# cvpal_v01.net
KiCad netlist of a schematic drawn in EAGLE
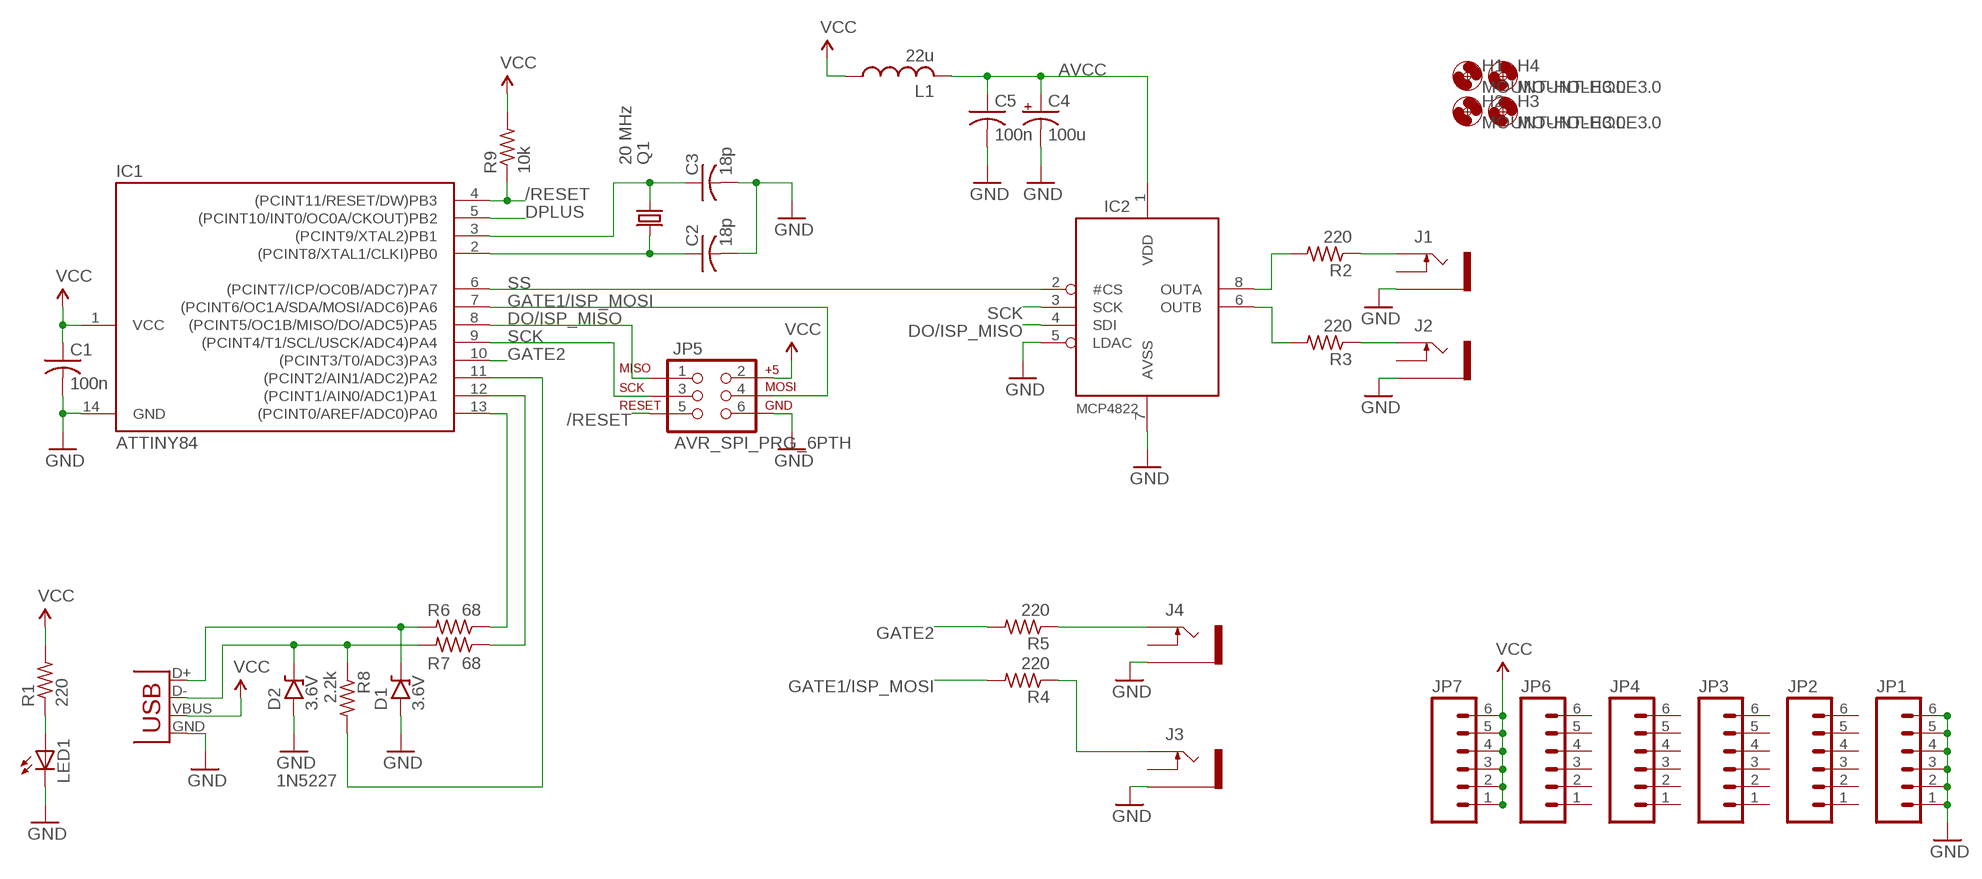
[diagram p0: schematic, sheet 1]

(export (version "E")
  (design (tool "Eeschema 10.0.6"))
  (components
    (comp (ref "C1")
      (value "100n")
      (footprint "eagle-import:C025-025X050")
      (libsource (lib "eagle-import") (part "C-US025-025X050"))
    )
    (comp (ref "C2")
      (value "18p")
      (footprint "eagle-import:C025-025X050")
      (libsource (lib "eagle-import") (part "C-US025-025X050"))
    )
    (comp (ref "C3")
      (value "18p")
      (footprint "eagle-import:C025-025X050")
      (libsource (lib "eagle-import") (part "C-US025-025X050"))
    )
    (comp (ref "C4")
      (value "100u")
      (footprint "eagle-import:E2,5-7")
      (libsource (lib "eagle-import") (part "CPOL-USE2.5-7"))
    )
    (comp (ref "C5")
      (value "100n")
      (footprint "eagle-import:C025-025X050")
      (libsource (lib "eagle-import") (part "C-US025-025X050"))
    )
    (comp (ref "D1")
      (value "3.6V")
      (footprint "eagle-import:D-5")
      (libsource (lib "eagle-import") (part "1N47XXDO35"))
    )
    (comp (ref "D2")
      (value "3.6V")
      (footprint "eagle-import:D-5")
      (libsource (lib "eagle-import") (part "1N47XXDO35"))
    )
    (comp (ref "H1")
      (value "MOUNT-HOLE3.0")
      (footprint "eagle-import:3,0")
      (libsource (lib "eagle-import") (part "MOUNT-HOLE3.0"))
    )
    (comp (ref "H2")
      (value "MOUNT-HOLE3.0")
      (footprint "eagle-import:3,0")
      (libsource (lib "eagle-import") (part "MOUNT-HOLE3.0"))
    )
    (comp (ref "H3")
      (value "MOUNT-HOLE3.0")
      (footprint "eagle-import:3,0")
      (libsource (lib "eagle-import") (part "MOUNT-HOLE3.0"))
    )
    (comp (ref "H4")
      (value "MOUNT-HOLE3.0")
      (footprint "eagle-import:3,0")
      (libsource (lib "eagle-import") (part "MOUNT-HOLE3.0"))
    )
    (comp (ref "IC1")
      (value "ATTINY84")
      (footprint "eagle-import:DIL14")
      (libsource (lib "eagle-import") (part "ATTINY24/44/84-PU"))
    )
    (comp (ref "IC2")
      (value "MCP4822")
      (footprint "eagle-import:DIL08")
      (libsource (lib "eagle-import") (part "MCP4822"))
    )
    (comp (ref "J1")
      (value "1503_12")
      (footprint "eagle-import:1503_12")
      (libsource (lib "eagle-import") (part "1503_12"))
    )
    (comp (ref "J2")
      (value "1503_12")
      (footprint "eagle-import:1503_12")
      (libsource (lib "eagle-import") (part "1503_12"))
    )
    (comp (ref "J3")
      (value "1503_12")
      (footprint "eagle-import:1503_12")
      (libsource (lib "eagle-import") (part "1503_12"))
    )
    (comp (ref "J4")
      (value "1503_12")
      (footprint "eagle-import:1503_12")
      (libsource (lib "eagle-import") (part "1503_12"))
    )
    (comp (ref "JP1")
      (value "M06SIP")
      (footprint "eagle-import:1X06")
      (libsource (lib "eagle-import") (part "M06SIP"))
    )
    (comp (ref "JP2")
      (value "M06SIP")
      (footprint "eagle-import:1X06")
      (libsource (lib "eagle-import") (part "M06SIP"))
    )
    (comp (ref "JP3")
      (value "M06SIP")
      (footprint "eagle-import:1X06")
      (libsource (lib "eagle-import") (part "M06SIP"))
    )
    (comp (ref "JP4")
      (value "M06SIP")
      (footprint "eagle-import:1X06")
      (libsource (lib "eagle-import") (part "M06SIP"))
    )
    (comp (ref "JP5")
      (value "AVR_SPI_PRG_6PTH")
      (footprint "eagle-import:2X3")
      (libsource (lib "eagle-import") (part "AVR_SPI_PRG_6PTH"))
    )
    (comp (ref "JP6")
      (value "M06SIP")
      (footprint "eagle-import:1X06")
      (libsource (lib "eagle-import") (part "M06SIP"))
    )
    (comp (ref "JP7")
      (value "M06SIP")
      (footprint "eagle-import:1X06")
      (libsource (lib "eagle-import") (part "M06SIP"))
    )
    (comp (ref "L1")
      (value "22u")
      (footprint "eagle-import:0207_10")
      (libsource (lib "eagle-import") (part "L-US0207/10"))
    )
    (comp (ref "LED1")
      (value "LED5MM")
      (footprint "eagle-import:LED5MM")
      (libsource (lib "eagle-import") (part "LED5MM"))
    )
    (comp (ref "Q1")
      (value "20 MHz")
      (footprint "eagle-import:HC49_S")
      (libsource (lib "eagle-import") (part "CRYSTALHC49S"))
    )
    (comp (ref "R1")
      (value "220")
      (footprint "eagle-import:0204_7")
      (libsource (lib "eagle-import") (part "R-US_0204/7"))
    )
    (comp (ref "R2")
      (value "220")
      (footprint "eagle-import:0204_7")
      (libsource (lib "eagle-import") (part "R-US_0204/7"))
    )
    (comp (ref "R3")
      (value "220")
      (footprint "eagle-import:0204_7")
      (libsource (lib "eagle-import") (part "R-US_0204/7"))
    )
    (comp (ref "R4")
      (value "220")
      (footprint "eagle-import:0204_7")
      (libsource (lib "eagle-import") (part "R-US_0204/7"))
    )
    (comp (ref "R5")
      (value "220")
      (footprint "eagle-import:0204_7")
      (libsource (lib "eagle-import") (part "R-US_0204/7"))
    )
    (comp (ref "R6")
      (value "68")
      (footprint "eagle-import:0204_7")
      (libsource (lib "eagle-import") (part "R-US_0204/7"))
    )
    (comp (ref "R7")
      (value "68")
      (footprint "eagle-import:0204_7")
      (libsource (lib "eagle-import") (part "R-US_0204/7"))
    )
    (comp (ref "R8")
      (value "2.2k")
      (footprint "eagle-import:0204_7")
      (libsource (lib "eagle-import") (part "R-US_0204/7"))
    )
    (comp (ref "R9")
      (value "10k")
      (footprint "eagle-import:0204_7")
      (libsource (lib "eagle-import") (part "R-US_0204/7"))
    )
    (comp (ref "X2")
      (value "USBPTH")
      (footprint "eagle-import:USB-B-PTH")
      (libsource (lib "eagle-import") (part "USBPTH"))
    )
  )
  (nets
    (net (code "1") (name "/AVCC") (class "Default")
      (node (ref "C4") (pin "+") (pinfunction "+_+") (pintype "passive"))
      (node (ref "C5") (pin "1") (pinfunction "1_1") (pintype "passive"))
      (node (ref "IC2") (pin "1") (pinfunction "VDD_1") (pintype "power_in"))
      (node (ref "L1") (pin "2") (pinfunction "2_2") (pintype "passive"))
    )
    (net (code "2") (name "/DO{slash}ISP_MISO") (class "Default")
      (node (ref "IC1") (pin "8") (pinfunction "(PCINT5/OC1B/MISO/DO/ADC5)PA5_8") (pintype "bidirectional"))
      (node (ref "IC2") (pin "4") (pinfunction "SDI_4") (pintype "input"))
      (node (ref "JP5") (pin "1") (pinfunction "1_1") (pintype "passive"))
    )
    (net (code "3") (name "/DPLUS") (class "Default")
      (node (ref "IC1") (pin "13") (pinfunction "(PCINT0/AREF/ADC0)PA0_13") (pintype "bidirectional"))
      (node (ref "IC1") (pin "5") (pinfunction "(PCINT10/INT0/OC0A/CKOUT)PB2_5") (pintype "bidirectional"))
      (node (ref "R6") (pin "1") (pinfunction "1_1") (pintype "passive"))
    )
    (net (code "4") (name "/GATE1{slash}ISP_MOSI") (class "Default")
      (node (ref "IC1") (pin "7") (pinfunction "(PCINT6/OC1A/SDA/MOSI/ADC6)PA6_7") (pintype "bidirectional"))
      (node (ref "JP5") (pin "4") (pinfunction "4_4") (pintype "passive"))
      (node (ref "R4") (pin "2") (pinfunction "2_2") (pintype "passive"))
    )
    (net (code "5") (name "/GATE2") (class "Default")
      (node (ref "IC1") (pin "10") (pinfunction "(PCINT3/T0/ADC3)PA3_10") (pintype "bidirectional"))
      (node (ref "R5") (pin "2") (pinfunction "2_2") (pintype "passive"))
    )
    (net (code "6") (name "/SCK") (class "Default")
      (node (ref "IC1") (pin "9") (pinfunction "(PCINT4/T1/SCL/USCK/ADC4)PA4_9") (pintype "bidirectional"))
      (node (ref "IC2") (pin "3") (pinfunction "SCK_3") (pintype "input"))
      (node (ref "JP5") (pin "3") (pinfunction "3_3") (pintype "passive"))
    )
    (net (code "7") (name "/SS") (class "Default")
      (node (ref "IC1") (pin "6") (pinfunction "(PCINT7/ICP/OC0B/ADC7)PA7_6") (pintype "bidirectional"))
      (node (ref "IC2") (pin "2") (pinfunction "#CS_2") (pintype "input"))
    )
    (net (code "8") (name "/{slash}RESET") (class "Default")
      (node (ref "IC1") (pin "4") (pinfunction "(PCINT11/RESET/DW)PB3_4") (pintype "bidirectional"))
      (node (ref "JP5") (pin "5") (pinfunction "5_5") (pintype "passive"))
      (node (ref "R9") (pin "1") (pinfunction "1_1") (pintype "passive"))
    )
    (net (code "9") (name "GND") (class "Default")
      (node (ref "C1") (pin "2") (pinfunction "2_2") (pintype "passive"))
      (node (ref "C2") (pin "2") (pinfunction "2_2") (pintype "passive"))
      (node (ref "C3") (pin "2") (pinfunction "2_2") (pintype "passive"))
      (node (ref "C4") (pin "-") (pinfunction "-_-") (pintype "passive"))
      (node (ref "C5") (pin "2") (pinfunction "2_2") (pintype "passive"))
      (node (ref "D1") (pin "A") (pinfunction "A_A") (pintype "passive"))
      (node (ref "D2") (pin "A") (pinfunction "A_A") (pintype "passive"))
      (node (ref "IC1") (pin "14") (pinfunction "GND_14") (pintype "power_in"))
      (node (ref "IC2") (pin "5") (pinfunction "LDAC_5") (pintype "input"))
      (node (ref "IC2") (pin "7") (pinfunction "AVSS_7") (pintype "power_in"))
      (node (ref "J1") (pin "5") (pinfunction "1_5") (pintype "passive"))
      (node (ref "J2") (pin "5") (pinfunction "1_5") (pintype "passive"))
      (node (ref "J3") (pin "5") (pinfunction "1_5") (pintype "passive"))
      (node (ref "J4") (pin "5") (pinfunction "1_5") (pintype "passive"))
      (node (ref "JP1") (pin "1") (pinfunction "1_1") (pintype "passive"))
      (node (ref "JP1") (pin "2") (pinfunction "2_2") (pintype "passive"))
      (node (ref "JP1") (pin "3") (pinfunction "3_3") (pintype "passive"))
      (node (ref "JP1") (pin "4") (pinfunction "4_4") (pintype "passive"))
      (node (ref "JP1") (pin "5") (pinfunction "5_5") (pintype "passive"))
      (node (ref "JP1") (pin "6") (pinfunction "6_6") (pintype "passive"))
      (node (ref "JP5") (pin "6") (pinfunction "6_6") (pintype "passive"))
      (node (ref "LED1") (pin "K") (pinfunction "C_K") (pintype "passive"))
      (node (ref "X2") (pin "GND") (pinfunction "GND_GND") (pintype "bidirectional"))
    )
    (net (code "10") (name "Net-(D1-PadC)") (class "Default")
      (node (ref "D1") (pin "C") (pinfunction "C_C") (pintype "passive"))
      (node (ref "R6") (pin "2") (pinfunction "2_2") (pintype "passive"))
      (node (ref "X2") (pin "D+") (pinfunction "D+_D+") (pintype "bidirectional"))
    )
    (net (code "11") (name "Net-(D2-PadC)") (class "Default")
      (node (ref "D2") (pin "C") (pinfunction "C_C") (pintype "passive"))
      (node (ref "R7") (pin "2") (pinfunction "2_2") (pintype "passive"))
      (node (ref "R8") (pin "1") (pinfunction "1_1") (pintype "passive"))
      (node (ref "X2") (pin "D-") (pinfunction "D-_D-") (pintype "bidirectional"))
    )
    (net (code "12") (name "Net-(IC1-(PCINT1{slash}AIN0{slash}ADC1)PA1)") (class "Default")
      (node (ref "IC1") (pin "12") (pinfunction "(PCINT1/AIN0/ADC1)PA1_12") (pintype "bidirectional"))
      (node (ref "R7") (pin "1") (pinfunction "1_1") (pintype "passive"))
    )
    (net (code "13") (name "Net-(IC1-(PCINT2{slash}AIN1{slash}ADC2)PA2)") (class "Default")
      (node (ref "IC1") (pin "11") (pinfunction "(PCINT2/AIN1/ADC2)PA2_11") (pintype "bidirectional"))
      (node (ref "R8") (pin "2") (pinfunction "2_2") (pintype "passive"))
    )
    (net (code "14") (name "Net-(IC1-(PCINT8{slash}XTAL1{slash}CLKI)PB0)") (class "Default")
      (node (ref "C2") (pin "1") (pinfunction "1_1") (pintype "passive"))
      (node (ref "IC1") (pin "2") (pinfunction "(PCINT8/XTAL1/CLKI)PB0_2") (pintype "bidirectional"))
      (node (ref "Q1") (pin "2") (pinfunction "2_2") (pintype "passive"))
    )
    (net (code "15") (name "Net-(IC1-(PCINT9{slash}XTAL2)PB1)") (class "Default")
      (node (ref "C3") (pin "1") (pinfunction "1_1") (pintype "passive"))
      (node (ref "IC1") (pin "3") (pinfunction "(PCINT9/XTAL2)PB1_3") (pintype "bidirectional"))
      (node (ref "Q1") (pin "1") (pinfunction "1_1") (pintype "passive"))
    )
    (net (code "16") (name "Net-(IC2-OUTA)") (class "Default")
      (node (ref "IC2") (pin "8") (pinfunction "OUTA_8") (pintype "output"))
      (node (ref "R2") (pin "2") (pinfunction "2_2") (pintype "passive"))
    )
    (net (code "17") (name "Net-(IC2-OUTB)") (class "Default")
      (node (ref "IC2") (pin "6") (pinfunction "OUTB_6") (pintype "output"))
      (node (ref "R3") (pin "2") (pinfunction "2_2") (pintype "passive"))
    )
    (net (code "18") (name "Net-(J1-2)") (class "Default")
      (node (ref "J1") (pin "3") (pinfunction "2_3") (pintype "passive"))
      (node (ref "R2") (pin "1") (pinfunction "1_1") (pintype "passive"))
    )
    (net (code "19") (name "Net-(J2-2)") (class "Default")
      (node (ref "J2") (pin "3") (pinfunction "2_3") (pintype "passive"))
      (node (ref "R3") (pin "1") (pinfunction "1_1") (pintype "passive"))
    )
    (net (code "20") (name "Net-(J3-2)") (class "Default")
      (node (ref "J3") (pin "3") (pinfunction "2_3") (pintype "passive"))
      (node (ref "R4") (pin "1") (pinfunction "1_1") (pintype "passive"))
    )
    (net (code "21") (name "Net-(J4-2)") (class "Default")
      (node (ref "J4") (pin "3") (pinfunction "2_3") (pintype "passive"))
      (node (ref "R5") (pin "1") (pinfunction "1_1") (pintype "passive"))
    )
    (net (code "22") (name "Net-(LED1-PadA)") (class "Default")
      (node (ref "LED1") (pin "A") (pinfunction "A_A") (pintype "passive"))
      (node (ref "R1") (pin "1") (pinfunction "1_1") (pintype "passive"))
    )
    (net (code "23") (name "VCC") (class "Default")
      (node (ref "C1") (pin "1") (pinfunction "1_1") (pintype "passive"))
      (node (ref "IC1") (pin "1") (pinfunction "VCC_1") (pintype "power_in"))
      (node (ref "JP5") (pin "2") (pinfunction "2_2") (pintype "passive"))
      (node (ref "JP7") (pin "1") (pinfunction "1_1") (pintype "passive"))
      (node (ref "JP7") (pin "2") (pinfunction "2_2") (pintype "passive"))
      (node (ref "JP7") (pin "3") (pinfunction "3_3") (pintype "passive"))
      (node (ref "JP7") (pin "4") (pinfunction "4_4") (pintype "passive"))
      (node (ref "JP7") (pin "5") (pinfunction "5_5") (pintype "passive"))
      (node (ref "JP7") (pin "6") (pinfunction "6_6") (pintype "passive"))
      (node (ref "L1") (pin "1") (pinfunction "1_1") (pintype "passive"))
      (node (ref "R1") (pin "2") (pinfunction "2_2") (pintype "passive"))
      (node (ref "R9") (pin "2") (pinfunction "2_2") (pintype "passive"))
      (node (ref "X2") (pin "VBUS") (pinfunction "VBUS_VBUS") (pintype "bidirectional"))
    )
    (net (code "24") (name "unconnected-(J1-3-Pad4)") (class "Default")
      (node (ref "J1") (pin "4") (pinfunction "3_4") (pintype "passive"))
    )
    (net (code "25") (name "unconnected-(J2-3-Pad4)") (class "Default")
      (node (ref "J2") (pin "4") (pinfunction "3_4") (pintype "passive"))
    )
    (net (code "26") (name "unconnected-(J3-3-Pad4)") (class "Default")
      (node (ref "J3") (pin "4") (pinfunction "3_4") (pintype "passive"))
    )
    (net (code "27") (name "unconnected-(J4-3-Pad4)") (class "Default")
      (node (ref "J4") (pin "4") (pinfunction "3_4") (pintype "passive"))
    )
    (net (code "28") (name "unconnected-(JP2-Pad1)") (class "Default")
      (node (ref "JP2") (pin "1") (pinfunction "1_1") (pintype "passive"))
    )
    (net (code "29") (name "unconnected-(JP2-Pad2)") (class "Default")
      (node (ref "JP2") (pin "2") (pinfunction "2_2") (pintype "passive"))
    )
    (net (code "30") (name "unconnected-(JP2-Pad3)") (class "Default")
      (node (ref "JP2") (pin "3") (pinfunction "3_3") (pintype "passive"))
    )
    (net (code "31") (name "unconnected-(JP2-Pad4)") (class "Default")
      (node (ref "JP2") (pin "4") (pinfunction "4_4") (pintype "passive"))
    )
    (net (code "32") (name "unconnected-(JP2-Pad5)") (class "Default")
      (node (ref "JP2") (pin "5") (pinfunction "5_5") (pintype "passive"))
    )
    (net (code "33") (name "unconnected-(JP2-Pad6)") (class "Default")
      (node (ref "JP2") (pin "6") (pinfunction "6_6") (pintype "passive"))
    )
    (net (code "34") (name "unconnected-(JP3-Pad1)") (class "Default")
      (node (ref "JP3") (pin "1") (pinfunction "1_1") (pintype "passive"))
    )
    (net (code "35") (name "unconnected-(JP3-Pad2)") (class "Default")
      (node (ref "JP3") (pin "2") (pinfunction "2_2") (pintype "passive"))
    )
    (net (code "36") (name "unconnected-(JP3-Pad3)") (class "Default")
      (node (ref "JP3") (pin "3") (pinfunction "3_3") (pintype "passive"))
    )
    (net (code "37") (name "unconnected-(JP3-Pad4)") (class "Default")
      (node (ref "JP3") (pin "4") (pinfunction "4_4") (pintype "passive"))
    )
    (net (code "38") (name "unconnected-(JP3-Pad5)") (class "Default")
      (node (ref "JP3") (pin "5") (pinfunction "5_5") (pintype "passive"))
    )
    (net (code "39") (name "unconnected-(JP3-Pad6)") (class "Default")
      (node (ref "JP3") (pin "6") (pinfunction "6_6") (pintype "passive"))
    )
    (net (code "40") (name "unconnected-(JP4-Pad1)") (class "Default")
      (node (ref "JP4") (pin "1") (pinfunction "1_1") (pintype "passive"))
    )
    (net (code "41") (name "unconnected-(JP4-Pad2)") (class "Default")
      (node (ref "JP4") (pin "2") (pinfunction "2_2") (pintype "passive"))
    )
    (net (code "42") (name "unconnected-(JP4-Pad3)") (class "Default")
      (node (ref "JP4") (pin "3") (pinfunction "3_3") (pintype "passive"))
    )
    (net (code "43") (name "unconnected-(JP4-Pad4)") (class "Default")
      (node (ref "JP4") (pin "4") (pinfunction "4_4") (pintype "passive"))
    )
    (net (code "44") (name "unconnected-(JP4-Pad5)") (class "Default")
      (node (ref "JP4") (pin "5") (pinfunction "5_5") (pintype "passive"))
    )
    (net (code "45") (name "unconnected-(JP4-Pad6)") (class "Default")
      (node (ref "JP4") (pin "6") (pinfunction "6_6") (pintype "passive"))
    )
    (net (code "46") (name "unconnected-(JP6-Pad1)") (class "Default")
      (node (ref "JP6") (pin "1") (pinfunction "1_1") (pintype "passive"))
    )
    (net (code "47") (name "unconnected-(JP6-Pad2)") (class "Default")
      (node (ref "JP6") (pin "2") (pinfunction "2_2") (pintype "passive"))
    )
    (net (code "48") (name "unconnected-(JP6-Pad3)") (class "Default")
      (node (ref "JP6") (pin "3") (pinfunction "3_3") (pintype "passive"))
    )
    (net (code "49") (name "unconnected-(JP6-Pad4)") (class "Default")
      (node (ref "JP6") (pin "4") (pinfunction "4_4") (pintype "passive"))
    )
    (net (code "50") (name "unconnected-(JP6-Pad5)") (class "Default")
      (node (ref "JP6") (pin "5") (pinfunction "5_5") (pintype "passive"))
    )
    (net (code "51") (name "unconnected-(JP6-Pad6)") (class "Default")
      (node (ref "JP6") (pin "6") (pinfunction "6_6") (pintype "passive"))
    )
  )
)
